# MAIN_STM32F301K8U6.net
KiCad netlist of a schematic drawn in Altium Designer
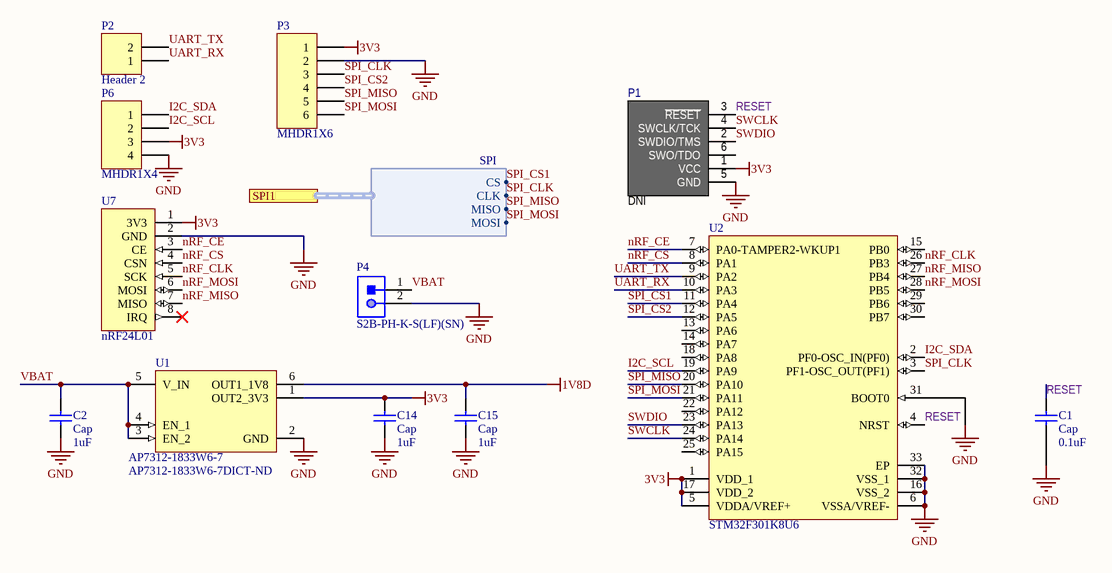
[diagram p0: MAIN_STM32F301K8U6.SchDoc]

(export (version "E")
  (design (tool "Eeschema 10.0.6"))
  (components
    (comp (ref "C1")
      (value "Cap")
      (footprint "CAPC1005N")
      (description "Capacitor")
      (fields (field (name "ALTIUM_VALUE") "0.1uF") (field (name "PUBLISHER") "Altium Limited"))
      (libsource (lib "Miscellaneous Devices") (part "Cap"))
    )
    (comp (ref "C2")
      (value "Cap")
      (footprint "CAPC1005N")
      (description "Capacitor")
      (fields (field (name "ALTIUM_VALUE") "1uF") (field (name "PUBLISHER") "Altium Limited"))
      (libsource (lib "Miscellaneous Devices") (part "Cap"))
    )
    (comp (ref "C14")
      (value "Cap")
      (footprint "CAPC1005N")
      (description "Capacitor")
      (fields (field (name "ALTIUM_VALUE") "1uF") (field (name "PUBLISHER") "Altium Limited"))
      (libsource (lib "Miscellaneous Devices") (part "Cap"))
    )
    (comp (ref "C15")
      (value "Cap")
      (footprint "CAPC1005N")
      (description "Capacitor")
      (fields (field (name "ALTIUM_VALUE") "1uF") (field (name "PUBLISHER") "Altium Limited"))
      (libsource (lib "Miscellaneous Devices") (part "Cap"))
    )
    (comp (ref "P1") (value "DNI") (footprint "TC2030-NL") (libsource (lib "TagConnect") (part "TC2030-CTX")))
    (comp (ref "P2")
      (value "Header 2")
      (footprint "MHDR1X2")
      (description "Header, 2-Pin")
      (fields (field (name "PUBLISHER") "Altium Limited"))
      (libsource (lib "Miscellaneous Connectors") (part "Header 2"))
    )
    (comp (ref "P3")
      (value "MHDR1X6")
      (footprint "MHDR1X6")
      (description "Header, 6-Pin")
      (fields (field (name "PUBLISHER") "Altium Limited"))
      (libsource (lib "Miscellaneous Connectors") (part "MHDR1X6"))
    )
    (comp (ref "P4")
      (value "S2B-PH-K-S(LF)(SN)")
      (footprint "JST-S2B-PH-K-S_V")
      (fields (field (name "TOLERANCE") "20%"))
      (libsource (lib "Altium Content Vault") (part "CN-1P-M-R2"))
    )
    (comp (ref "P6")
      (value "MHDR1X4")
      (footprint "MHDR1X4")
      (description "Header, 4-Pin")
      (fields (field (name "PUBLISHER") "Altium Limited"))
      (libsource (lib "Miscellaneous Connectors") (part "MHDR1X4"))
    )
    (comp (ref "U1")
      (value "AP7312-1833W6-7")
      (footprint "SOT95P285X145-6N")
      (description "IC REG LINEAR 1.8V/3.3V SOT26")
      (fields (field (name "SUPPLIER PART NUMBER 1") "AP7312-1833W6-7DICT-ND"))
      (libsource (lib "Schlib1") (part "AP7312-1833W6-7"))
    )
    (comp (ref "U2")
      (value "STM32F301K8U6")
      (footprint "STM-UFQFPN32_L")
      (libsource (lib "Altium Content Vault") (part "MC-ARM-STM32F301-UFQFPN32"))
    )
    (comp (ref "U7") (value "nRF24L01") (footprint "MHDR1X8") (libsource (lib "Schlib2") (part "nRF24L01")))
  )
  (nets
    (net (code "2") (name "/I2C_SCL") (class "Default")
      (node (ref "P6") (pin "2") (pinfunction "2_2") (pintype "passive"))
      (node (ref "U2") (pin "19") (pinfunction "PA9_19") (pintype "bidirectional"))
    )
    (net (code "3") (name "/I2C_SDA") (class "Default")
      (node (ref "P6") (pin "1") (pinfunction "1_1") (pintype "passive"))
      (node (ref "U2") (pin "2") (pinfunction "PF0-OSC_IN(PF0)_2") (pintype "bidirectional"))
    )
    (net (code "4") (name "/RESET") (class "Default")
      (node (ref "C1") (pin "2") (pinfunction "2_2") (pintype "passive"))
      (node (ref "P1") (pin "3") (pinfunction "~{RESET}_3") (pintype "passive"))
      (node (ref "U2") (pin "4") (pinfunction "NRST_4") (pintype "bidirectional"))
    )
    (net (code "5") (name "/SPI_CLK") (class "Default")
      (node (ref "P3") (pin "3") (pinfunction "3_3") (pintype "passive"))
      (node (ref "U2") (pin "3") (pinfunction "PF1-OSC_OUT(PF1)_3") (pintype "bidirectional"))
    )
    (net (code "6") (name "/SPI_CS1") (class "Default")
      (node (ref "U2") (pin "11") (pinfunction "PA4_11") (pintype "bidirectional"))
    )
    (net (code "7") (name "/SPI_CS2") (class "Default")
      (node (ref "P3") (pin "4") (pinfunction "4_4") (pintype "passive"))
      (node (ref "U2") (pin "12") (pinfunction "PA5_12") (pintype "bidirectional"))
    )
    (net (code "8") (name "/SPI_MISO") (class "Default")
      (node (ref "P3") (pin "5") (pinfunction "5_5") (pintype "passive"))
      (node (ref "U2") (pin "20") (pinfunction "PA10_20") (pintype "bidirectional"))
    )
    (net (code "9") (name "/SPI_MOSI") (class "Default")
      (node (ref "P3") (pin "6") (pinfunction "6_6") (pintype "passive"))
      (node (ref "U2") (pin "21") (pinfunction "PA11_21") (pintype "bidirectional"))
    )
    (net (code "10") (name "/SWCLK") (class "Default")
      (node (ref "P1") (pin "4") (pinfunction "SWCLK/TCK_4") (pintype "passive"))
      (node (ref "U2") (pin "24") (pinfunction "PA14_24") (pintype "bidirectional"))
    )
    (net (code "11") (name "/SWDIO") (class "Default")
      (node (ref "P1") (pin "2") (pinfunction "SWDIO/TMS_2") (pintype "passive"))
      (node (ref "U2") (pin "23") (pinfunction "PA13_23") (pintype "bidirectional"))
    )
    (net (code "12") (name "/UART_RX") (class "Default")
      (node (ref "P2") (pin "1") (pinfunction "1_1") (pintype "passive"))
      (node (ref "U2") (pin "10") (pinfunction "PA3_10") (pintype "bidirectional"))
    )
    (net (code "13") (name "/UART_TX") (class "Default")
      (node (ref "P2") (pin "2") (pinfunction "2_2") (pintype "passive"))
      (node (ref "U2") (pin "9") (pinfunction "PA2_9") (pintype "bidirectional"))
    )
    (net (code "14") (name "/VBAT") (class "Default")
      (node (ref "C2") (pin "2") (pinfunction "2_2") (pintype "passive"))
      (node (ref "P4") (pin "1") (pinfunction "1_1") (pintype "passive"))
      (node (ref "U1") (pin "3") (pinfunction "EN_2_3") (pintype "input"))
      (node (ref "U1") (pin "4") (pinfunction "EN_1_4") (pintype "input"))
      (node (ref "U1") (pin "5") (pinfunction "V_IN_5") (pintype "power_in"))
    )
    (net (code "15") (name "/nRF_CE") (class "Default")
      (node (ref "U2") (pin "7") (pinfunction "PA0-TAMPER2-WKUP1_7") (pintype "bidirectional"))
      (node (ref "U7") (pin "3") (pinfunction "CE_3") (pintype "input"))
    )
    (net (code "16") (name "/nRF_CLK") (class "Default")
      (node (ref "U2") (pin "26") (pinfunction "PB3_26") (pintype "bidirectional"))
      (node (ref "U7") (pin "5") (pinfunction "SCK_5") (pintype "input"))
    )
    (net (code "17") (name "/nRF_CS") (class "Default")
      (node (ref "U2") (pin "8") (pinfunction "PA1_8") (pintype "bidirectional"))
      (node (ref "U7") (pin "4") (pinfunction "CSN_4") (pintype "input"))
    )
    (net (code "18") (name "/nRF_MISO") (class "Default")
      (node (ref "U2") (pin "27") (pinfunction "PB4_27") (pintype "bidirectional"))
      (node (ref "U7") (pin "7") (pinfunction "MISO_7") (pintype "bidirectional"))
    )
    (net (code "19") (name "/nRF_MOSI") (class "Default")
      (node (ref "U2") (pin "28") (pinfunction "PB5_28") (pintype "bidirectional"))
      (node (ref "U7") (pin "6") (pinfunction "MOSI_6") (pintype "bidirectional"))
    )
    (net (code "21") (name "1V8D") (class "Default")
      (node (ref "C15") (pin "2") (pinfunction "2_2") (pintype "passive"))
      (node (ref "U1") (pin "6") (pinfunction "OUT1_1V8_6") (pintype "power_in"))
    )
    (net (code "22") (name "3V3") (class "Default")
      (node (ref "C14") (pin "2") (pinfunction "2_2") (pintype "passive"))
      (node (ref "P1") (pin "1") (pinfunction "VCC_1") (pintype "passive"))
      (node (ref "P3") (pin "1") (pinfunction "1_1") (pintype "passive"))
      (node (ref "P6") (pin "3") (pinfunction "3_3") (pintype "passive"))
      (node (ref "U1") (pin "1") (pinfunction "OUT2_3V3_1") (pintype "power_in"))
      (node (ref "U2") (pin "1") (pinfunction "VDD_1_1") (pintype "power_in"))
      (node (ref "U2") (pin "17") (pinfunction "VDD_2_17") (pintype "power_in"))
      (node (ref "U2") (pin "5") (pinfunction "VDDA/VREF+_5") (pintype "power_in"))
      (node (ref "U7") (pin "1") (pinfunction "3V3_1") (pintype "power_in"))
    )
    (net (code "23") (name "GND") (class "Default")
      (node (ref "C1") (pin "1") (pinfunction "1_1") (pintype "passive"))
      (node (ref "C14") (pin "1") (pinfunction "1_1") (pintype "passive"))
      (node (ref "C15") (pin "1") (pinfunction "1_1") (pintype "passive"))
      (node (ref "C2") (pin "1") (pinfunction "1_1") (pintype "passive"))
      (node (ref "P1") (pin "5") (pinfunction "GND_5") (pintype "passive"))
      (node (ref "P3") (pin "2") (pinfunction "2_2") (pintype "passive"))
      (node (ref "P4") (pin "2") (pinfunction "2_2") (pintype "passive"))
      (node (ref "P6") (pin "4") (pinfunction "4_4") (pintype "passive"))
      (node (ref "U1") (pin "2") (pinfunction "GND_2") (pintype "power_in"))
      (node (ref "U2") (pin "16") (pinfunction "VSS_2_16") (pintype "power_in"))
      (node (ref "U2") (pin "31") (pinfunction "BOOT0_31") (pintype "input"))
      (node (ref "U2") (pin "32") (pinfunction "VSS_1_32") (pintype "power_in"))
      (node (ref "U2") (pin "33") (pinfunction "EP_33") (pintype "passive"))
      (node (ref "U2") (pin "6") (pinfunction "VSSA/VREF-_6") (pintype "power_in"))
      (node (ref "U7") (pin "2") (pinfunction "GND_2") (pintype "power_in"))
    )
    (net (code "24") (name "unconnected-(P1-SWO{slash}TDO-Pad6)") (class "Default")
      (node (ref "P1") (pin "6") (pinfunction "SWO/TDO_6") (pintype "passive"))
    )
    (net (code "25") (name "unconnected-(U2-PA6-Pad13)") (class "Default")
      (node (ref "U2") (pin "13") (pinfunction "PA6_13") (pintype "bidirectional"))
    )
    (net (code "26") (name "unconnected-(U2-PA7-Pad14)") (class "Default")
      (node (ref "U2") (pin "14") (pinfunction "PA7_14") (pintype "bidirectional"))
    )
    (net (code "27") (name "unconnected-(U2-PA8-Pad18)") (class "Default")
      (node (ref "U2") (pin "18") (pinfunction "PA8_18") (pintype "bidirectional"))
    )
    (net (code "28") (name "unconnected-(U2-PA12-Pad22)") (class "Default")
      (node (ref "U2") (pin "22") (pinfunction "PA12_22") (pintype "bidirectional"))
    )
    (net (code "29") (name "unconnected-(U2-PA15-Pad25)") (class "Default")
      (node (ref "U2") (pin "25") (pinfunction "PA15_25") (pintype "bidirectional"))
    )
    (net (code "30") (name "unconnected-(U2-PB0-Pad15)") (class "Default")
      (node (ref "U2") (pin "15") (pinfunction "PB0_15") (pintype "bidirectional"))
    )
    (net (code "31") (name "unconnected-(U2-PB6-Pad29)") (class "Default")
      (node (ref "U2") (pin "29") (pinfunction "PB6_29") (pintype "bidirectional"))
    )
    (net (code "32") (name "unconnected-(U2-PB7-Pad30)") (class "Default")
      (node (ref "U2") (pin "30") (pinfunction "PB7_30") (pintype "bidirectional"))
    )
    (net (code "33") (name "unconnected-(U7-IRQ-Pad8)") (class "Default")
      (node (ref "U7") (pin "8") (pinfunction "IRQ_8") (pintype "output+no_connect"))
    )
  )
)
